# UserInterface_0_V1_01.net
KiCad netlist of a schematic drawn in Altium Designer
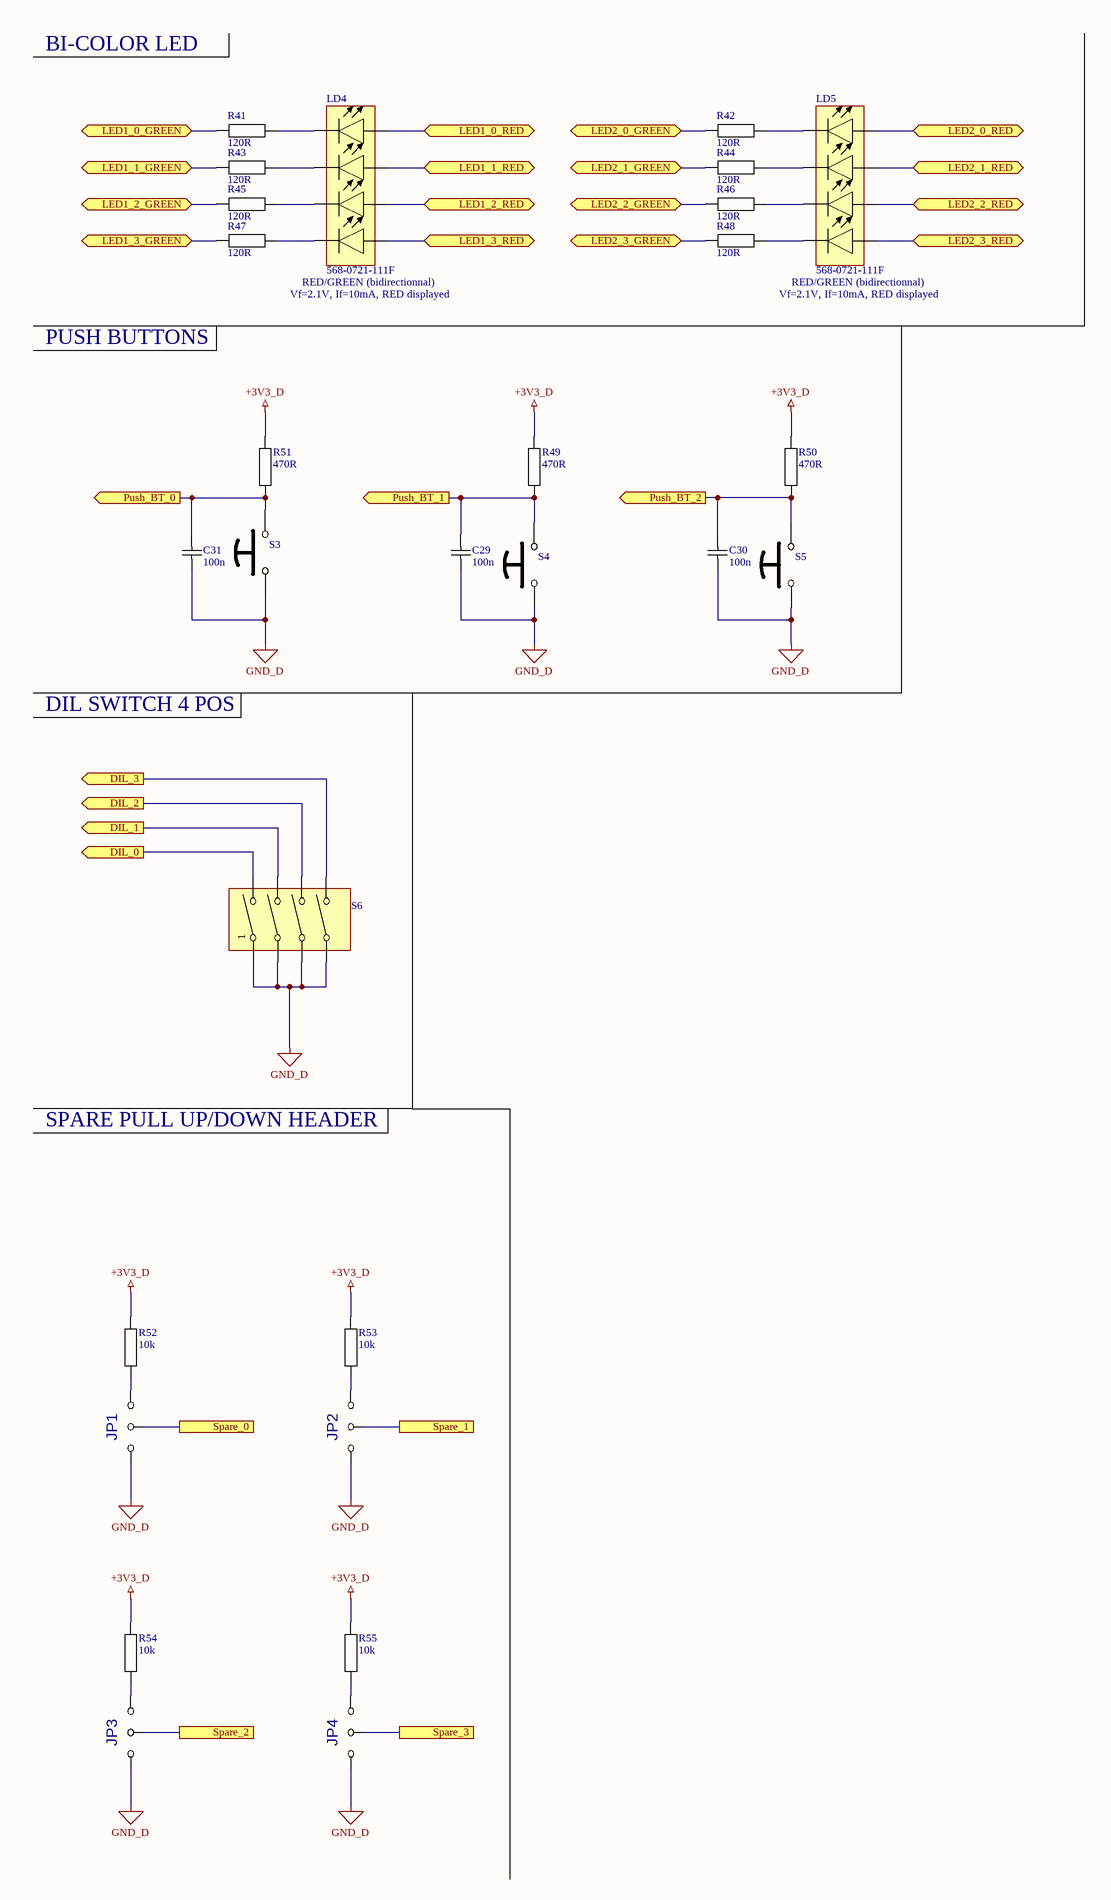
[diagram p0: UserInterface_0_V1_01.SchDoc, left]
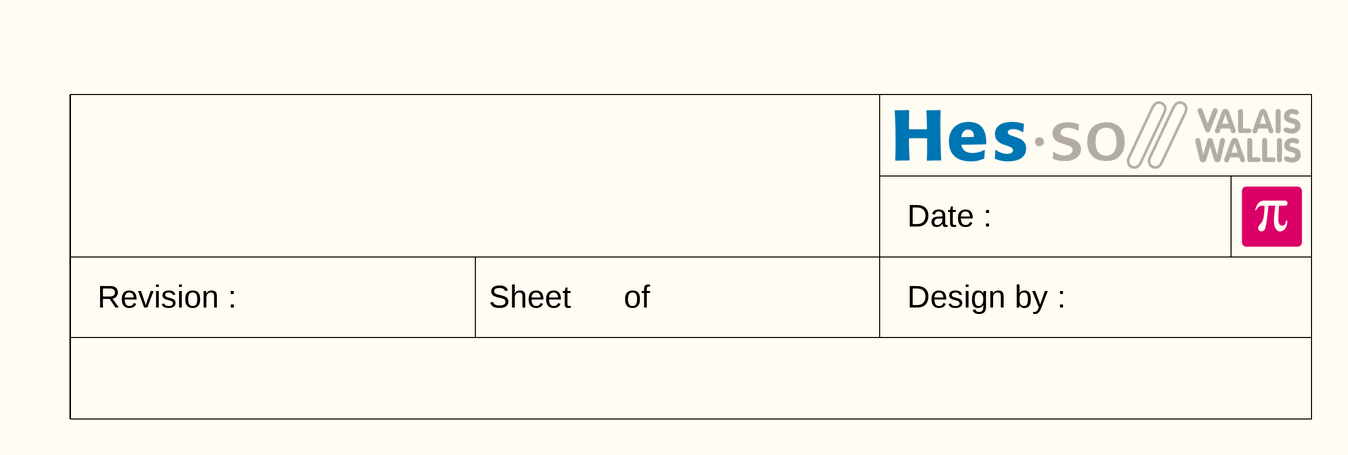
[diagram p1: UserInterface_0_V1_01.SchDoc, right]

(export (version "E")
  (design (tool "Eeschema 10.0.6"))
  (components
    (comp (ref "C29")
      (value "100n")
      (footprint "CAPACITOR 1608 REFLOW")
      (description "Capacitor X7R 10% 50V 2012(0805)")
      (libsource (lib "Capacitor") (part "Capacitor"))
    )
    (comp (ref "C30")
      (value "100n")
      (footprint "CAPACITOR 1608 REFLOW")
      (description "Capacitor X7R 10% 50V 2012(0805)")
      (libsource (lib "Capacitor") (part "Capacitor"))
    )
    (comp (ref "C31")
      (value "100n")
      (footprint "CAPACITOR 1608 REFLOW")
      (description "Capacitor X7R 10% 50V 2012(0805)")
      (libsource (lib "Capacitor") (part "Capacitor"))
    )
    (comp (ref "JP1")
      (value "{Value}")
      (footprint "JUMPER3 SMD 2012")
      (description "JUMPER 3 POS")
      (libsource (lib "Jumper") (part "JUMPER 3 POS"))
    )
    (comp (ref "JP2")
      (value "{Value}")
      (footprint "JUMPER3 SMD 2012")
      (description "JUMPER 3 POS")
      (libsource (lib "Jumper") (part "JUMPER 3 POS"))
    )
    (comp (ref "JP3")
      (value "{Value}")
      (footprint "JUMPER3 SMD 2012")
      (description "JUMPER 3 POS")
      (libsource (lib "Jumper") (part "JUMPER 3 POS"))
    )
    (comp (ref "JP4")
      (value "{Value}")
      (footprint "JUMPER3 SMD 2012")
      (description "JUMPER 3 POS")
      (libsource (lib "Jumper") (part "JUMPER 3 POS"))
    )
    (comp (ref "LD4")
      (value "568-0721-111F")
      (footprint "LED Dialight 568-0721-111")
      (description "LED Dialight 568-0721-111F")
      (fields (field (name "MANUFACTURER") "Dialight"))
      (libsource (lib "Diode") (part "LED Dialight 568-0721-111F"))
    )
    (comp (ref "LD5")
      (value "568-0721-111F")
      (footprint "LED Dialight 568-0721-111")
      (description "LED Dialight 568-0721-111F")
      (fields (field (name "MANUFACTURER") "Dialight"))
      (libsource (lib "Diode") (part "LED Dialight 568-0721-111F"))
    )
    (comp (ref "R41")
      (value "120R")
      (footprint "RESISTOR 1608 REFLOW")
      (description "Resistor 1% 50V 100mW 1608(0603)")
      (libsource (lib "Resistor") (part "Resistor"))
    )
    (comp (ref "R42")
      (value "120R")
      (footprint "RESISTOR 1608 REFLOW")
      (description "Resistor 1% 50V 100mW 1608(0603)")
      (libsource (lib "Resistor") (part "Resistor"))
    )
    (comp (ref "R43")
      (value "120R")
      (footprint "RESISTOR 1608 REFLOW")
      (description "Resistor 1% 50V 100mW 1608(0603)")
      (libsource (lib "Resistor") (part "Resistor"))
    )
    (comp (ref "R44")
      (value "120R")
      (footprint "RESISTOR 1608 REFLOW")
      (description "Resistor 1% 50V 100mW 1608(0603)")
      (libsource (lib "Resistor") (part "Resistor"))
    )
    (comp (ref "R45")
      (value "120R")
      (footprint "RESISTOR 1608 REFLOW")
      (description "Resistor 1% 50V 100mW 1608(0603)")
      (libsource (lib "Resistor") (part "Resistor"))
    )
    (comp (ref "R46")
      (value "120R")
      (footprint "RESISTOR 1608 REFLOW")
      (description "Resistor 1% 50V 100mW 1608(0603)")
      (libsource (lib "Resistor") (part "Resistor"))
    )
    (comp (ref "R47")
      (value "120R")
      (footprint "RESISTOR 1608 REFLOW")
      (description "Resistor 1% 50V 100mW 1608(0603)")
      (libsource (lib "Resistor") (part "Resistor"))
    )
    (comp (ref "R48")
      (value "120R")
      (footprint "RESISTOR 1608 REFLOW")
      (description "Resistor 1% 50V 100mW 1608(0603)")
      (libsource (lib "Resistor") (part "Resistor"))
    )
    (comp (ref "R49")
      (value "470R")
      (footprint "RESISTOR 1608 REFLOW")
      (description "Resistor 1% 50V 125mW 2012(0805)")
      (libsource (lib "Resistor") (part "Resistor"))
    )
    (comp (ref "R50")
      (value "470R")
      (footprint "RESISTOR 1608 REFLOW")
      (description "Resistor 1% 50V 125mW 2012(0805)")
      (libsource (lib "Resistor") (part "Resistor"))
    )
    (comp (ref "R51")
      (value "470R")
      (footprint "RESISTOR 1608 REFLOW")
      (description "Resistor 1% 50V 125mW 2012(0805)")
      (libsource (lib "Resistor") (part "Resistor"))
    )
    (comp (ref "R52")
      (value "10k")
      (footprint "RESISTOR 1608 REFLOW")
      (description "Resistor 1% 50V 125mW 2012(0805)")
      (libsource (lib "Resistor") (part "Resistor"))
    )
    (comp (ref "R53")
      (value "10k")
      (footprint "RESISTOR 1608 REFLOW")
      (description "Resistor 1% 50V 125mW 2012(0805)")
      (libsource (lib "Resistor") (part "Resistor"))
    )
    (comp (ref "R54")
      (value "10k")
      (footprint "RESISTOR 1608 REFLOW")
      (description "Resistor 1% 50V 125mW 2012(0805)")
      (libsource (lib "Resistor") (part "Resistor"))
    )
    (comp (ref "R55")
      (value "10k")
      (footprint "RESISTOR 1608 REFLOW")
      (description "Resistor 1% 50V 125mW 2012(0805)")
      (libsource (lib "Resistor") (part "Resistor"))
    )
    (comp (ref "S3")
      (value "FSMRA4JH04")
      (footprint "Push Button C7.1x3.7 TE FSMRA4JH")
      (description "Push Button, 2 pins")
      (fields (field (name "MANUFACTURER") "TE Connectivity / Alcoswitch"))
      (libsource (lib "Button") (part "Push Button 2Pins"))
    )
    (comp (ref "S4")
      (value "FSMRA4JH04")
      (footprint "Push Button C7.1x3.7 TE FSMRA4JH")
      (description "Push Button, 2 pins")
      (fields (field (name "MANUFACTURER") "TE Connectivity / Alcoswitch"))
      (libsource (lib "Button") (part "Push Button 2Pins"))
    )
    (comp (ref "S5")
      (value "FSMRA4JH04")
      (footprint "Push Button C7.1x3.7 TE FSMRA4JH")
      (description "Push Button, 2 pins")
      (fields (field (name "MANUFACTURER") "TE Connectivity / Alcoswitch"))
      (libsource (lib "Button") (part "Push Button 2Pins"))
    )
    (comp (ref "S6")
      (value "*")
      (footprint "DIP SWITCH MULTICOMP  MCDHN-04F")
      (description "MULTICOMP  MCDHN-04F")
      (libsource (lib "Button") (part "DIP Switch 4Pos"))
    )
  )
  (nets
    (net (code "1") (name "+3V3_D") (class "Default")
      (node (ref "R49") (pin "2") (pinfunction "2_2") (pintype "passive"))
      (node (ref "R50") (pin "2") (pinfunction "2_2") (pintype "passive"))
      (node (ref "R51") (pin "2") (pinfunction "2_2") (pintype "passive"))
      (node (ref "R52") (pin "2") (pinfunction "2_2") (pintype "passive"))
      (node (ref "R53") (pin "2") (pinfunction "2_2") (pintype "passive"))
      (node (ref "R54") (pin "2") (pinfunction "2_2") (pintype "passive"))
      (node (ref "R55") (pin "2") (pinfunction "2_2") (pintype "passive"))
    )
    (net (code "2") (name "/DIL_0") (class "Default")
      (node (ref "S6") (pin "2") (pinfunction "2_2") (pintype "passive"))
    )
    (net (code "3") (name "/DIL_1") (class "Default")
      (node (ref "S6") (pin "4") (pinfunction "4_4") (pintype "passive"))
    )
    (net (code "4") (name "/DIL_2") (class "Default")
      (node (ref "S6") (pin "6") (pinfunction "6_6") (pintype "passive"))
    )
    (net (code "5") (name "/DIL_3") (class "Default")
      (node (ref "S6") (pin "8") (pinfunction "8_8") (pintype "passive"))
    )
    (net (code "6") (name "/LED1_0_GREEN") (class "Default")
      (node (ref "R41") (pin "1") (pinfunction "1_1") (pintype "passive"))
    )
    (net (code "7") (name "/LED1_0_RED") (class "Default")
      (node (ref "LD4") (pin "8") (pinfunction "A_8") (pintype "passive"))
    )
    (net (code "8") (name "/LED1_1_GREEN") (class "Default")
      (node (ref "R43") (pin "1") (pinfunction "1_1") (pintype "passive"))
    )
    (net (code "9") (name "/LED1_1_RED") (class "Default")
      (node (ref "LD4") (pin "6") (pinfunction "A_6") (pintype "passive"))
    )
    (net (code "10") (name "/LED1_2_GREEN") (class "Default")
      (node (ref "R45") (pin "1") (pinfunction "1_1") (pintype "passive"))
    )
    (net (code "11") (name "/LED1_2_RED") (class "Default")
      (node (ref "LD4") (pin "4") (pinfunction "A_4") (pintype "passive"))
    )
    (net (code "12") (name "/LED1_3_GREEN") (class "Default")
      (node (ref "R47") (pin "1") (pinfunction "1_1") (pintype "passive"))
    )
    (net (code "13") (name "/LED1_3_RED") (class "Default")
      (node (ref "LD4") (pin "2") (pinfunction "A_2") (pintype "passive"))
    )
    (net (code "14") (name "/LED2_0_GREEN") (class "Default")
      (node (ref "R42") (pin "1") (pinfunction "1_1") (pintype "passive"))
    )
    (net (code "15") (name "/LED2_0_RED") (class "Default")
      (node (ref "LD5") (pin "8") (pinfunction "A_8") (pintype "passive"))
    )
    (net (code "16") (name "/LED2_1_GREEN") (class "Default")
      (node (ref "R44") (pin "1") (pinfunction "1_1") (pintype "passive"))
    )
    (net (code "17") (name "/LED2_1_RED") (class "Default")
      (node (ref "LD5") (pin "6") (pinfunction "A_6") (pintype "passive"))
    )
    (net (code "18") (name "/LED2_2_GREEN") (class "Default")
      (node (ref "R46") (pin "1") (pinfunction "1_1") (pintype "passive"))
    )
    (net (code "19") (name "/LED2_2_RED") (class "Default")
      (node (ref "LD5") (pin "4") (pinfunction "A_4") (pintype "passive"))
    )
    (net (code "20") (name "/LED2_3_GREEN") (class "Default")
      (node (ref "R48") (pin "1") (pinfunction "1_1") (pintype "passive"))
    )
    (net (code "21") (name "/LED2_3_RED") (class "Default")
      (node (ref "LD5") (pin "2") (pinfunction "A_2") (pintype "passive"))
    )
    (net (code "22") (name "/Push_BT_0") (class "Default")
      (node (ref "C31") (pin "2") (pinfunction "2_2") (pintype "passive"))
      (node (ref "R51") (pin "1") (pinfunction "1_1") (pintype "passive"))
      (node (ref "S3") (pin "2") (pinfunction "2_2") (pintype "passive"))
    )
    (net (code "23") (name "/Push_BT_1") (class "Default")
      (node (ref "C29") (pin "2") (pinfunction "2_2") (pintype "passive"))
      (node (ref "R49") (pin "1") (pinfunction "1_1") (pintype "passive"))
      (node (ref "S4") (pin "2") (pinfunction "2_2") (pintype "passive"))
    )
    (net (code "24") (name "/Push_BT_2") (class "Default")
      (node (ref "C30") (pin "2") (pinfunction "2_2") (pintype "passive"))
      (node (ref "R50") (pin "1") (pinfunction "1_1") (pintype "passive"))
      (node (ref "S5") (pin "2") (pinfunction "2_2") (pintype "passive"))
    )
    (net (code "25") (name "/Spare_0") (class "Default")
      (node (ref "JP1") (pin "2") (pinfunction "2_2") (pintype "passive"))
    )
    (net (code "26") (name "/Spare_1") (class "Default")
      (node (ref "JP2") (pin "2") (pinfunction "2_2") (pintype "passive"))
    )
    (net (code "27") (name "/Spare_2") (class "Default")
      (node (ref "JP3") (pin "2") (pinfunction "2_2") (pintype "passive"))
    )
    (net (code "28") (name "/Spare_3") (class "Default")
      (node (ref "JP4") (pin "2") (pinfunction "2_2") (pintype "passive"))
    )
    (net (code "29") (name "GND_D") (class "Default")
      (node (ref "C29") (pin "1") (pinfunction "1_1") (pintype "passive"))
      (node (ref "C30") (pin "1") (pinfunction "1_1") (pintype "passive"))
      (node (ref "C31") (pin "1") (pinfunction "1_1") (pintype "passive"))
      (node (ref "JP1") (pin "1") (pinfunction "1_1") (pintype "passive"))
      (node (ref "JP2") (pin "1") (pinfunction "1_1") (pintype "passive"))
      (node (ref "JP3") (pin "1") (pinfunction "1_1") (pintype "passive"))
      (node (ref "JP4") (pin "1") (pinfunction "1_1") (pintype "passive"))
      (node (ref "S3") (pin "1") (pinfunction "1_1") (pintype "passive"))
      (node (ref "S4") (pin "1") (pinfunction "1_1") (pintype "passive"))
      (node (ref "S5") (pin "1") (pinfunction "1_1") (pintype "passive"))
      (node (ref "S6") (pin "1") (pinfunction "1_1") (pintype "passive"))
      (node (ref "S6") (pin "3") (pinfunction "3_3") (pintype "passive"))
      (node (ref "S6") (pin "5") (pinfunction "5_5") (pintype "passive"))
      (node (ref "S6") (pin "7") (pinfunction "7_7") (pintype "passive"))
    )
    (net (code "30") (name "Net-(JP1-Pad3)") (class "Default")
      (node (ref "JP1") (pin "3") (pinfunction "3_3") (pintype "passive"))
      (node (ref "R52") (pin "1") (pinfunction "1_1") (pintype "passive"))
    )
    (net (code "31") (name "Net-(JP2-Pad3)") (class "Default")
      (node (ref "JP2") (pin "3") (pinfunction "3_3") (pintype "passive"))
      (node (ref "R53") (pin "1") (pinfunction "1_1") (pintype "passive"))
    )
    (net (code "32") (name "Net-(JP3-Pad3)") (class "Default")
      (node (ref "JP3") (pin "3") (pinfunction "3_3") (pintype "passive"))
      (node (ref "R54") (pin "1") (pinfunction "1_1") (pintype "passive"))
    )
    (net (code "33") (name "Net-(JP4-Pad3)") (class "Default")
      (node (ref "JP4") (pin "3") (pinfunction "3_3") (pintype "passive"))
      (node (ref "R55") (pin "1") (pinfunction "1_1") (pintype "passive"))
    )
    (net (code "34") (name "Net-(LD4-C-Pad1)") (class "Default")
      (node (ref "LD4") (pin "1") (pinfunction "C_1") (pintype "passive"))
      (node (ref "R47") (pin "2") (pinfunction "2_2") (pintype "passive"))
    )
    (net (code "35") (name "Net-(LD4-C-Pad3)") (class "Default")
      (node (ref "LD4") (pin "3") (pinfunction "C_3") (pintype "passive"))
      (node (ref "R45") (pin "2") (pinfunction "2_2") (pintype "passive"))
    )
    (net (code "36") (name "Net-(LD4-C-Pad5)") (class "Default")
      (node (ref "LD4") (pin "5") (pinfunction "C_5") (pintype "passive"))
      (node (ref "R43") (pin "2") (pinfunction "2_2") (pintype "passive"))
    )
    (net (code "37") (name "Net-(LD4-C-Pad7)") (class "Default")
      (node (ref "LD4") (pin "7") (pinfunction "C_7") (pintype "passive"))
      (node (ref "R41") (pin "2") (pinfunction "2_2") (pintype "passive"))
    )
    (net (code "38") (name "Net-(LD5-C-Pad1)") (class "Default")
      (node (ref "LD5") (pin "1") (pinfunction "C_1") (pintype "passive"))
      (node (ref "R48") (pin "2") (pinfunction "2_2") (pintype "passive"))
    )
    (net (code "39") (name "Net-(LD5-C-Pad3)") (class "Default")
      (node (ref "LD5") (pin "3") (pinfunction "C_3") (pintype "passive"))
      (node (ref "R46") (pin "2") (pinfunction "2_2") (pintype "passive"))
    )
    (net (code "40") (name "Net-(LD5-C-Pad5)") (class "Default")
      (node (ref "LD5") (pin "5") (pinfunction "C_5") (pintype "passive"))
      (node (ref "R44") (pin "2") (pinfunction "2_2") (pintype "passive"))
    )
    (net (code "41") (name "Net-(LD5-C-Pad7)") (class "Default")
      (node (ref "LD5") (pin "7") (pinfunction "C_7") (pintype "passive"))
      (node (ref "R42") (pin "2") (pinfunction "2_2") (pintype "passive"))
    )
  )
)
